# master.net
KiCad netlist of a schematic drawn in EAGLE
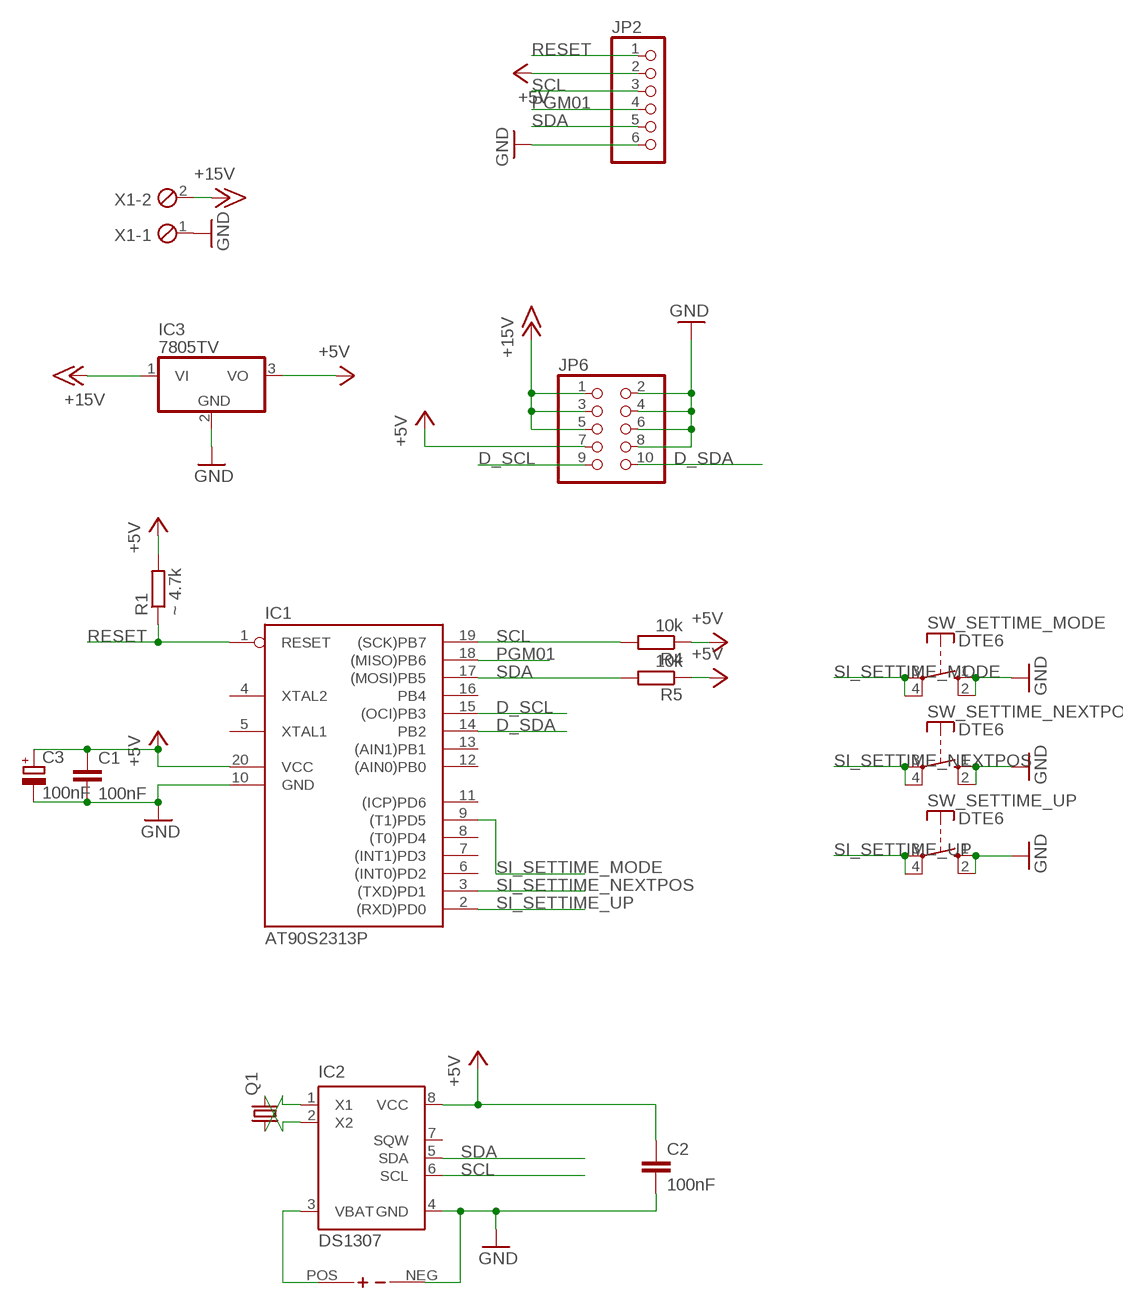
[diagram p0: schematic, sheet 1]

(export (version "E")
  (design (tool "Eeschema 10.0.6"))
  (components
    (comp (ref "C1")
      (value "100nF")
      (footprint "eagle-import:C0805")
      (libsource (lib "eagle-import") (part "C-EUC0805"))
    )
    (comp (ref "C2")
      (value "100nF")
      (footprint "eagle-import:C0805")
      (libsource (lib "eagle-import") (part "C-EUC0805"))
    )
    (comp (ref "C3")
      (value "100nF")
      (footprint "eagle-import:E2,5-7")
      (libsource (lib "eagle-import") (part "CPOL-EUE2.5-7"))
    )
    (comp (ref "IC1")
      (value "AT90S2313P")
      (footprint "eagle-import:DIL20")
      (libsource (lib "eagle-import") (part "AT90S2313P"))
    )
    (comp (ref "IC2")
      (value "DS1307")
      (footprint "eagle-import:DIP-8")
      (libsource (lib "eagle-import") (part "DS1307"))
    )
    (comp (ref "IC3")
      (value "7805TV")
      (footprint "eagle-import:TO220V")
      (libsource (lib "eagle-import") (part "78TV05"))
    )
    (comp (ref "JP2")
      (value "PINHD-1X6")
      (footprint "eagle-import:1X06")
      (libsource (lib "eagle-import") (part "PINHD-1X6"))
    )
    (comp (ref "JP6")
      (value "PINHD-2X5")
      (footprint "eagle-import:2X05")
      (libsource (lib "eagle-import") (part "PINHD-2X5"))
    )
    (comp (ref "Q1")
      (value "CRYSTALQ-SMD-1MM")
      (footprint "eagle-import:Q-SMD-1MM")
      (libsource (lib "eagle-import") (part "CRYSTALQ-SMD-1MM"))
    )
    (comp (ref "R1")
      (value "~ 4.7k")
      (footprint "eagle-import:0207_10")
      (libsource (lib "eagle-import") (part "R-EU_0207/10"))
    )
    (comp (ref "R4")
      (value "10k")
      (footprint "eagle-import:0207_10")
      (libsource (lib "eagle-import") (part "R-EU_0207/10"))
    )
    (comp (ref "R5")
      (value "10k")
      (footprint "eagle-import:0207_10")
      (libsource (lib "eagle-import") (part "R-EU_0207/10"))
    )
    (comp (ref "SW_SETTIME_MODE")
      (value "DTE6")
      (footprint "eagle-import:DTE6")
      (libsource (lib "eagle-import") (part "DTE6"))
    )
    (comp (ref "SW_SETTIME_NEXTPOS")
      (value "DTE6")
      (footprint "eagle-import:DTE6")
      (libsource (lib "eagle-import") (part "DTE6"))
    )
    (comp (ref "SW_SETTIME_UP")
      (value "DTE6")
      (footprint "eagle-import:DTE6")
      (libsource (lib "eagle-import") (part "DTE6"))
    )
    (comp (ref "U$1")
      (value "BATT")
      (footprint "eagle-import:BATT")
      (libsource (lib "eagle-import") (part "BATT"))
    )
    (comp (ref "X1")
      (value "MPT2")
      (footprint "eagle-import:2POL254")
      (libsource (lib "eagle-import") (part "MPT2"))
    )
  )
  (nets
    (net (code "1") (name "+5V") (class "Default")
      (node (ref "C1") (pin "1") (pinfunction "1_1") (pintype "passive"))
      (node (ref "C2") (pin "1") (pinfunction "1_1") (pintype "passive"))
      (node (ref "C3") (pin "+") (pinfunction "+_+") (pintype "passive"))
      (node (ref "IC1") (pin "20") (pinfunction "VCC_20") (pintype "power_in"))
      (node (ref "IC2") (pin "8") (pinfunction "VCC_8") (pintype "power_in"))
      (node (ref "IC3") (pin "3") (pinfunction "VO_3") (pintype "passive"))
      (node (ref "JP2") (pin "2") (pinfunction "2_2") (pintype "passive"))
      (node (ref "JP6") (pin "7") (pinfunction "7_7") (pintype "passive"))
      (node (ref "R1") (pin "2") (pinfunction "2_2") (pintype "passive"))
      (node (ref "R4") (pin "1") (pinfunction "1_1") (pintype "passive"))
      (node (ref "R5") (pin "1") (pinfunction "1_1") (pintype "passive"))
    )
    (net (code "2") (name "+15V") (class "Default")
      (node (ref "IC3") (pin "1") (pinfunction "VI_1") (pintype "input"))
      (node (ref "JP6") (pin "1") (pinfunction "1_1") (pintype "passive"))
      (node (ref "JP6") (pin "3") (pinfunction "3_3") (pintype "passive"))
      (node (ref "JP6") (pin "5") (pinfunction "5_5") (pintype "passive"))
      (node (ref "X1") (pin "2") (pinfunction "1_2") (pintype "passive"))
    )
    (net (code "3") (name "/D_SCL") (class "Default")
      (node (ref "IC1") (pin "15") (pinfunction "(OCI)PB3_15") (pintype "bidirectional"))
      (node (ref "JP6") (pin "9") (pinfunction "9_9") (pintype "passive"))
    )
    (net (code "4") (name "/D_SDA") (class "Default")
      (node (ref "IC1") (pin "14") (pinfunction "PB2_14") (pintype "bidirectional"))
      (node (ref "JP6") (pin "10") (pinfunction "10_10") (pintype "passive"))
    )
    (net (code "5") (name "/PGM01") (class "Default")
      (node (ref "IC1") (pin "18") (pinfunction "(MISO)PB6_18") (pintype "bidirectional"))
      (node (ref "JP2") (pin "4") (pinfunction "4_4") (pintype "passive"))
    )
    (net (code "6") (name "/RESET") (class "Default")
      (node (ref "IC1") (pin "1") (pinfunction "RESET_1") (pintype "bidirectional"))
      (node (ref "JP2") (pin "1") (pinfunction "1_1") (pintype "passive"))
      (node (ref "R1") (pin "1") (pinfunction "1_1") (pintype "passive"))
    )
    (net (code "7") (name "/SCL") (class "Default")
      (node (ref "IC1") (pin "19") (pinfunction "(SCK)PB7_19") (pintype "bidirectional"))
      (node (ref "IC2") (pin "6") (pinfunction "SCL_6") (pintype "input"))
      (node (ref "JP2") (pin "3") (pinfunction "3_3") (pintype "passive"))
      (node (ref "R4") (pin "2") (pinfunction "2_2") (pintype "passive"))
    )
    (net (code "8") (name "/SDA") (class "Default")
      (node (ref "IC1") (pin "17") (pinfunction "(MOSI)PB5_17") (pintype "bidirectional"))
      (node (ref "IC2") (pin "5") (pinfunction "SDA_5") (pintype "output"))
      (node (ref "JP2") (pin "5") (pinfunction "5_5") (pintype "passive"))
      (node (ref "R5") (pin "2") (pinfunction "2_2") (pintype "passive"))
    )
    (net (code "9") (name "/SI_SETTIME_MODE") (class "Default")
      (node (ref "IC1") (pin "9") (pinfunction "(T1)PD5_9") (pintype "bidirectional"))
      (node (ref "SW_SETTIME_MODE") (pin "3") (pinfunction "P_3") (pintype "passive"))
      (node (ref "SW_SETTIME_MODE") (pin "4") (pinfunction "P_4") (pintype "passive"))
    )
    (net (code "10") (name "/SI_SETTIME_NEXTPOS") (class "Default")
      (node (ref "IC1") (pin "3") (pinfunction "(TXD)PD1_3") (pintype "bidirectional"))
      (node (ref "SW_SETTIME_NEXTPOS") (pin "3") (pinfunction "P_3") (pintype "passive"))
      (node (ref "SW_SETTIME_NEXTPOS") (pin "4") (pinfunction "P_4") (pintype "passive"))
    )
    (net (code "11") (name "/SI_SETTIME_UP") (class "Default")
      (node (ref "IC1") (pin "2") (pinfunction "(RXD)PD0_2") (pintype "bidirectional"))
      (node (ref "SW_SETTIME_UP") (pin "3") (pinfunction "P_3") (pintype "passive"))
      (node (ref "SW_SETTIME_UP") (pin "4") (pinfunction "P_4") (pintype "passive"))
    )
    (net (code "12") (name "GND") (class "Default")
      (node (ref "C1") (pin "2") (pinfunction "2_2") (pintype "passive"))
      (node (ref "C2") (pin "2") (pinfunction "2_2") (pintype "passive"))
      (node (ref "C3") (pin "-") (pinfunction "-_-") (pintype "passive"))
      (node (ref "IC1") (pin "10") (pinfunction "GND_10") (pintype "power_in"))
      (node (ref "IC2") (pin "4") (pinfunction "GND_4") (pintype "power_in"))
      (node (ref "IC3") (pin "2") (pinfunction "GND_2") (pintype "passive"))
      (node (ref "JP2") (pin "6") (pinfunction "6_6") (pintype "passive"))
      (node (ref "JP6") (pin "2") (pinfunction "2_2") (pintype "passive"))
      (node (ref "JP6") (pin "4") (pinfunction "4_4") (pintype "passive"))
      (node (ref "JP6") (pin "6") (pinfunction "6_6") (pintype "passive"))
      (node (ref "JP6") (pin "8") (pinfunction "8_8") (pintype "passive"))
      (node (ref "SW_SETTIME_MODE") (pin "1") (pinfunction "S_1") (pintype "passive"))
      (node (ref "SW_SETTIME_MODE") (pin "2") (pinfunction "S_2") (pintype "passive"))
      (node (ref "SW_SETTIME_NEXTPOS") (pin "1") (pinfunction "S_1") (pintype "passive"))
      (node (ref "SW_SETTIME_NEXTPOS") (pin "2") (pinfunction "S_2") (pintype "passive"))
      (node (ref "SW_SETTIME_UP") (pin "1") (pinfunction "S_1") (pintype "passive"))
      (node (ref "SW_SETTIME_UP") (pin "2") (pinfunction "S_2") (pintype "passive"))
      (node (ref "U$1") (pin "NEG") (pinfunction "V-_NEG") (pintype "bidirectional"))
      (node (ref "X1") (pin "1") (pinfunction "1_1") (pintype "passive"))
    )
    (net (code "13") (name "Net-(IC2-VBAT)") (class "Default")
      (node (ref "IC2") (pin "3") (pinfunction "VBAT_3") (pintype "input"))
      (node (ref "U$1") (pin "POS") (pinfunction "V+_POS") (pintype "bidirectional"))
    )
    (net (code "14") (name "Net-(IC2-X1)") (class "Default")
      (node (ref "IC2") (pin "1") (pinfunction "X1_1") (pintype "input"))
      (node (ref "Q1") (pin "1") (pinfunction "1_1") (pintype "passive"))
    )
    (net (code "15") (name "Net-(IC2-X2)") (class "Default")
      (node (ref "IC2") (pin "2") (pinfunction "X2_2") (pintype "input"))
      (node (ref "Q1") (pin "2") (pinfunction "2_2") (pintype "passive"))
    )
    (net (code "16") (name "unconnected-(IC1-(AIN0)PB0-Pad12)") (class "Default")
      (node (ref "IC1") (pin "12") (pinfunction "(AIN0)PB0_12") (pintype "bidirectional"))
    )
    (net (code "17") (name "unconnected-(IC1-(AIN1)PB1-Pad13)") (class "Default")
      (node (ref "IC1") (pin "13") (pinfunction "(AIN1)PB1_13") (pintype "bidirectional"))
    )
    (net (code "18") (name "unconnected-(IC1-(ICP)PD6-Pad11)") (class "Default")
      (node (ref "IC1") (pin "11") (pinfunction "(ICP)PD6_11") (pintype "bidirectional"))
    )
    (net (code "19") (name "unconnected-(IC1-(INT0)PD2-Pad6)") (class "Default")
      (node (ref "IC1") (pin "6") (pinfunction "(INT0)PD2_6") (pintype "bidirectional"))
    )
    (net (code "20") (name "unconnected-(IC1-(INT1)PD3-Pad7)") (class "Default")
      (node (ref "IC1") (pin "7") (pinfunction "(INT1)PD3_7") (pintype "bidirectional"))
    )
    (net (code "21") (name "unconnected-(IC1-(T0)PD4-Pad8)") (class "Default")
      (node (ref "IC1") (pin "8") (pinfunction "(T0)PD4_8") (pintype "bidirectional"))
    )
    (net (code "22") (name "unconnected-(IC1-PB4-Pad16)") (class "Default")
      (node (ref "IC1") (pin "16") (pinfunction "PB4_16") (pintype "bidirectional"))
    )
    (net (code "23") (name "unconnected-(IC1-XTAL1-Pad5)") (class "Default")
      (node (ref "IC1") (pin "5") (pinfunction "XTAL1_5") (pintype "bidirectional"))
    )
    (net (code "24") (name "unconnected-(IC1-XTAL2-Pad4)") (class "Default")
      (node (ref "IC1") (pin "4") (pinfunction "XTAL2_4") (pintype "bidirectional"))
    )
    (net (code "25") (name "unconnected-(IC2-SQW-Pad7)") (class "Default")
      (node (ref "IC2") (pin "7") (pinfunction "SQW_7") (pintype "input"))
    )
  )
)
